# Galaxy.net
KiCad netlist of a schematic drawn in Altium Designer
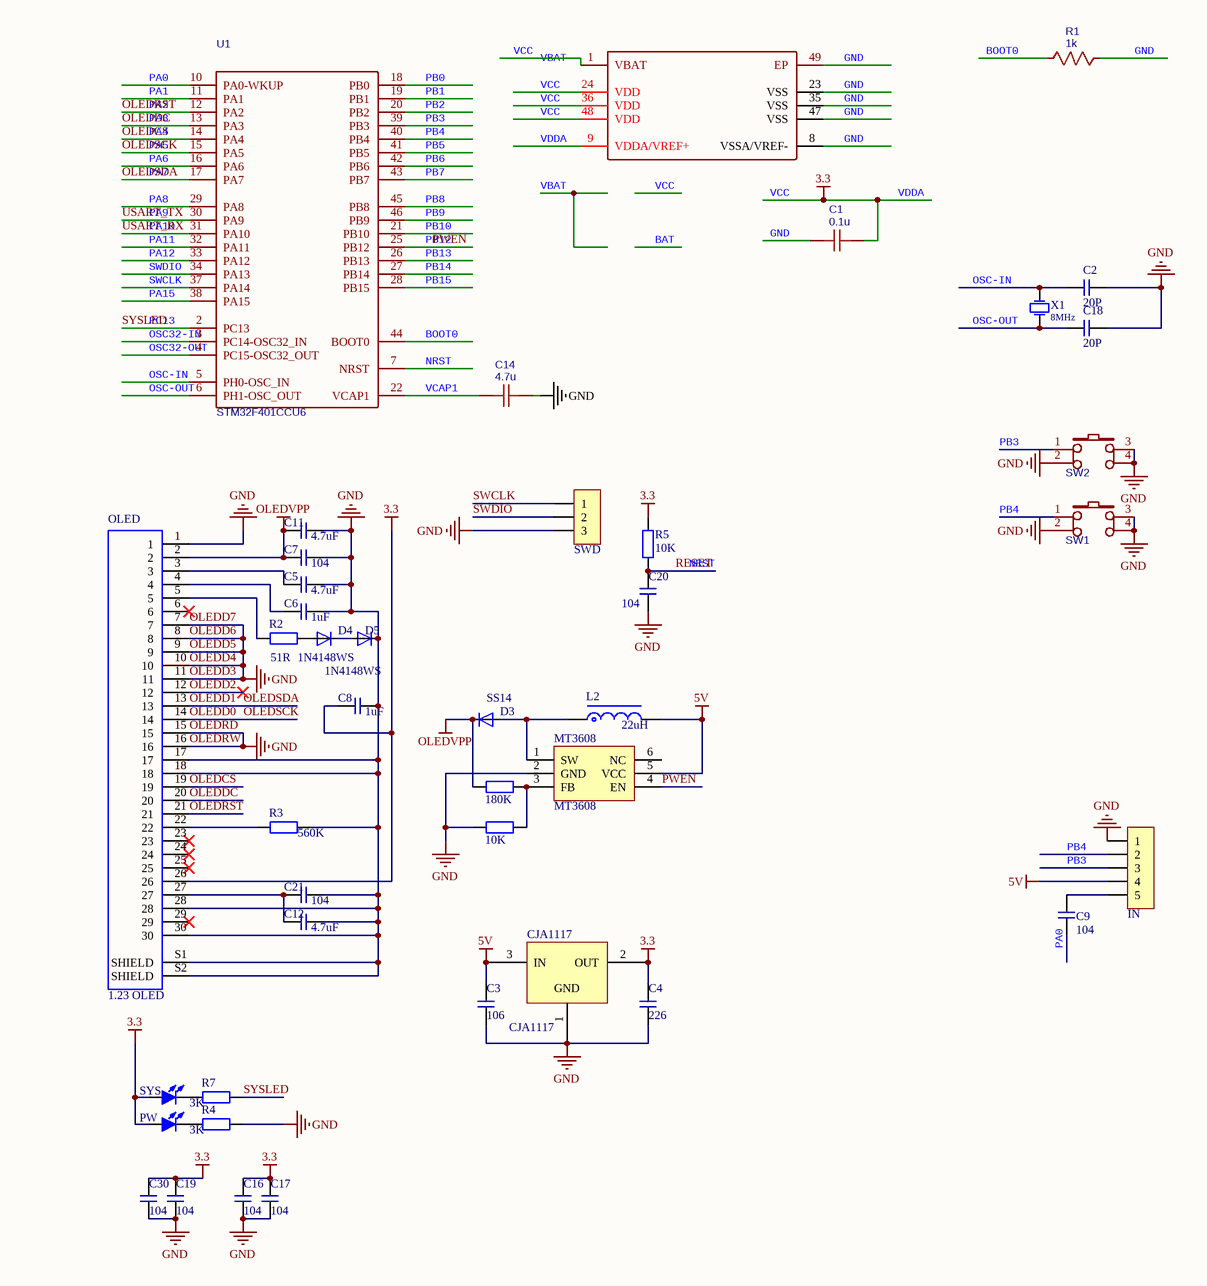
[diagram p0: Galaxy.SchDoc]

(export (version "E")
  (design (tool "Eeschema 10.0.6"))
  (components
    (comp (ref "C1")
      (value "0.1u")
      (footprint "0603C")
      (fields (field (name "CONTRIBUTOR") "LCEDA_Lib"))
      (libsource (lib "altium-import") (part "root_2_0.1u_"))
    )
    (comp (ref "C2") (value "20P") (footprint "0603C") (libsource (lib "Schlib1") (part "电容")))
    (comp (ref "C3") (value "106") (footprint "0603C") (libsource (lib "") (part "电容_1")))
    (comp (ref "C4") (value "226") (footprint "0603C") (libsource (lib "") (part "电容_1")))
    (comp (ref "C5") (value "4.7uF") (footprint "0603C") (libsource (lib "Schlib1") (part "电容")))
    (comp (ref "C6") (value "1uF") (footprint "0603C") (libsource (lib "Schlib1") (part "电容")))
    (comp (ref "C7") (value "104") (footprint "0603C") (libsource (lib "Schlib1") (part "电容")))
    (comp (ref "C8") (value "1uF") (footprint "0603C") (libsource (lib "Schlib1") (part "电容")))
    (comp (ref "C9") (value "104") (footprint "0603C") (libsource (lib "Schlib1") (part "电容")))
    (comp (ref "C11") (value "4.7uF") (footprint "0603C") (libsource (lib "Schlib1") (part "电容")))
    (comp (ref "C12") (value "4.7uF") (footprint "0603C") (libsource (lib "Schlib1") (part "电容")))
    (comp (ref "C14")
      (value "4.7u")
      (footprint "0603C")
      (fields (field (name "CONTRIBUTOR") "LCEDA_Lib"))
      (libsource (lib "altium-import") (part "root_0_4.7u_"))
    )
    (comp (ref "C16") (value "104") (footprint "0603C") (libsource (lib "Schlib1") (part "电容")))
    (comp (ref "C17") (value "104") (footprint "0603C") (libsource (lib "Schlib1") (part "电容")))
    (comp (ref "C18") (value "20P") (footprint "0603C") (libsource (lib "Schlib1") (part "电容")))
    (comp (ref "C19") (value "104") (footprint "0603C") (libsource (lib "Schlib1") (part "电容")))
    (comp (ref "C20") (value "104") (footprint "0603C") (libsource (lib "Schlib1") (part "电容")))
    (comp (ref "C21") (value "104") (footprint "0603C") (libsource (lib "Schlib1") (part "电容")))
    (comp (ref "C30") (value "104") (footprint "0603C") (libsource (lib "Schlib1") (part "电容")))
    (comp (ref "CJA1117") (value "CJA1117") (footprint "SOT-89-3") (libsource (lib "元件") (part "CJA1117")))
    (comp (ref "D3")
      (value "SS14")
      (footprint "SOD323_1N4148WS")
      (description "Diode Switching 75V 0.3A 2-Pin SOD-323 T/R")
      (fields (field (name "MF") "ON Semiconductor") (field (name "MP") "1N4148WS"))
      (libsource (lib "1N4148WS") (part "1N4148WS"))
    )
    (comp (ref "D4")
      (value "1N4148WS")
      (footprint "SOD323_1N4148WS")
      (description "Diode Switching 75V 0.3A 2-Pin SOD-323 T/R")
      (fields (field (name "MF") "ON Semiconductor"))
      (libsource (lib "1N4148WS") (part "1N4148WS"))
    )
    (comp (ref "D5")
      (value "1N4148WS")
      (footprint "SOD323_1N4148WS")
      (description "Diode Switching 75V 0.3A 2-Pin SOD-323 T/R")
      (fields (field (name "MF") "ON Semiconductor"))
      (libsource (lib "1N4148WS") (part "1N4148WS"))
    )
    (comp (ref "IN")
      (value "HDR-1X5")
      (footprint "ZH1.5-LS-5P")
      (description "5P接插件")
      (fields (field (name "版权归属") "源创客"))
      (libsource (lib "4.3   - 接插件-脚距1.5") (part "Header 5"))
    )
    (comp (ref "L2")
      (value "22uH")
      (footprint "1210-ec")
      (description "功率屏蔽电感")
      (fields (field (name "版权归属") "源创客"))
      (libsource (lib "3.1   - 电阻-电容-电感") (part "L-CDRH"))
    )
    (comp (ref "MT3608")
      (value "MT3608")
      (footprint "SOT23-6N")
      (description "可调升压芯片")
      (fields (field (name "版权归属") "源创客"))
      (libsource (lib "1.3   - 电源类芯片") (part "SX1308"))
    )
    (comp (ref "OLED")
      (value "1.23 OLED")
      (footprint "1.23 OLED")
      (description "FH12 Series 30 Position 0.5 mm Pitch Surface Mount Right Angle Flip Lock FFC/FPC")
      (fields (field (name "MF") "Hirose Electric") (field (name "MP") "FH12-30S-0.5SH_55_"))
      (libsource (lib "Nebula") (part "FH12-30S-0.5SH(55)"))
    )
    (comp (ref "PW")
      (value "白色")
      (footprint "0603LED")
      (description "方形LED")
      (fields (field (name "版权归属") "源创客"))
      (libsource (lib "9.1   - LED") (part "LED-F234"))
    )
    (comp (ref "R1")
      (value "1k")
      (footprint "0603R")
      (fields (field (name "CONTRIBUTOR") "LCEDA_Lib"))
      (libsource (lib "altium-import") (part "root_0_1k_"))
    )
    (comp (ref "R2")
      (value "51R")
      (footprint "0603R")
      (description "贴片电阻")
      (fields (field (name "版权归属") "源创客"))
      (libsource (lib "3.1   - 电阻-电容-电感") (part "R"))
    )
    (comp (ref "R3")
      (value "560K")
      (footprint "0603R")
      (description "贴片电阻")
      (fields (field (name "版权归属") "源创客"))
      (libsource (lib "3.1   - 电阻-电容-电感") (part "R"))
    )
    (comp (ref "R4")
      (value "3K")
      (footprint "0603R")
      (description "贴片电阻")
      (fields (field (name "版权归属") "源创客"))
      (libsource (lib "3.1   - 电阻-电容-电感") (part "R"))
    )
    (comp (ref "R5")
      (value "10K")
      (footprint "0603R")
      (description "贴片电阻")
      (fields (field (name "版权归属") "源创客"))
      (libsource (lib "3.1   - 电阻-电容-电感") (part "R"))
    )
    (comp (ref "R7")
      (value "3K")
      (footprint "0603R")
      (description "贴片电阻")
      (fields (field (name "版权归属") "源创客"))
      (libsource (lib "3.1   - 电阻-电容-电感") (part "R"))
    )
    (comp (ref "RB")
      (value "180K")
      (footprint "0603R")
      (description "贴片电阻")
      (fields (field (name "版权归属") "源创客"))
      (libsource (lib "3.1   - 电阻-电容-电感") (part "R"))
    )
    (comp (ref "RS")
      (value "10K")
      (footprint "0603R")
      (description "贴片电阻")
      (fields (field (name "版权归属") "源创客"))
      (libsource (lib "3.1   - 电阻-电容-电感") (part "R"))
    )
    (comp (ref "SW1")
      (value "Button-SMD-4x4x1.5")
      (footprint "SW-SMD_TS-1086E-16")
      (fields
        (field (name "BOM_SUPPLIER PART") "C71830")
        (field (name "BOM_MANUFACTURER PART") "4*4*1.5Copper head,260G, 0.25mm,")
      )
      (libsource (lib "altium-import") (part "root_0_Button-SMD-4x4x1.5_"))
    )
    (comp (ref "SW2")
      (value "Button-SMD-4x4x1.5")
      (footprint "SW-SMD_TS-1086E-16")
      (fields
        (field (name "BOM_SUPPLIER PART") "C71830")
        (field (name "BOM_MANUFACTURER PART") "4*4*1.5Copper head,260G, 0.25mm,")
      )
      (libsource (lib "altium-import") (part "root_0_Button-SMD-4x4x1.5_"))
    )
    (comp (ref "SWD")
      (value "HDR-1X3")
      (footprint "ZH1.5-LI-3P")
      (description "3P接插件")
      (fields (field (name "版权归属") "源创客"))
      (libsource (lib "4.3   - 接插件-脚距1.5") (part "Header 3"))
    )
    (comp (ref "SYS")
      (value "粉色")
      (footprint "0603LED")
      (description "方形LED")
      (fields (field (name "版权归属") "源创客"))
      (libsource (lib "9.1   - LED") (part "LED-F234"))
    )
    (comp (ref "U1")
      (value "STM32F401CCU6")
      (footprint "UFQFPN-48_L7.0-W7.0-P0.50-BL-EP")
      (fields (field (name "BOM_SUPPLIER PART") "C79861") (field (name "SUBPART_NO") "1"))
      (libsource (lib "Galaxy") (part "STM32F401CCU6"))
    )
    (comp (ref "X1")
      (value "8MHz")
      (footprint "OSC 5032-2P")
      (description "XTAL,8MHz,±20PPM,12.6*4.5")
      (fields (field (name "Comment") "1.6.1.01.005.001"))
      (libsource (lib "Mark_7") (part "1.6.1.01.005.001"))
    )
  )
  (nets
    (net (code "2") (name "/BOOT0") (class "Default")
      (node (ref "R1") (pin "1") (pinfunction "1_1") (pintype "passive"))
      (node (ref "U1") (pin "44") (pinfunction "BOOT0_44") (pintype "passive"))
    )
    (net (code "3") (name "/NRST") (class "Default")
      (node (ref "C20") (pin "1") (pinfunction "1_1") (pintype "passive"))
      (node (ref "R5") (pin "2") (pinfunction "2_2") (pintype "passive"))
      (node (ref "U1") (pin "7") (pinfunction "NRST_7") (pintype "passive"))
    )
    (net (code "4") (name "/OLEDCS") (class "Default")
      (node (ref "OLED") (pin "19") (pinfunction "19_19") (pintype "passive"))
      (node (ref "U1") (pin "14") (pinfunction "PA4_14") (pintype "passive"))
    )
    (net (code "5") (name "/OLEDD0") (class "Default")
      (node (ref "OLED") (pin "14") (pinfunction "14_14") (pintype "passive"))
      (node (ref "U1") (pin "15") (pinfunction "PA5_15") (pintype "passive"))
    )
    (net (code "6") (name "/OLEDD1") (class "Default")
      (node (ref "OLED") (pin "13") (pinfunction "13_13") (pintype "passive"))
      (node (ref "U1") (pin "17") (pinfunction "PA7_17") (pintype "passive"))
    )
    (net (code "7") (name "/OLEDD2") (class "Default")
      (node (ref "OLED") (pin "12") (pinfunction "12_12") (pintype "passive+no_connect"))
    )
    (net (code "8") (name "/OLEDDC") (class "Default")
      (node (ref "OLED") (pin "20") (pinfunction "20_20") (pintype "passive"))
      (node (ref "U1") (pin "13") (pinfunction "PA3_13") (pintype "passive"))
    )
    (net (code "9") (name "/OLEDRST") (class "Default")
      (node (ref "OLED") (pin "21") (pinfunction "21_21") (pintype "passive"))
      (node (ref "U1") (pin "12") (pinfunction "PA2_12") (pintype "passive"))
    )
    (net (code "10") (name "/OSC-IN") (class "Default")
      (node (ref "C2") (pin "2") (pinfunction "2_2") (pintype "passive"))
      (node (ref "U1") (pin "5") (pinfunction "PH0-OSC_IN_5") (pintype "passive"))
      (node (ref "X1") (pin "1") (pinfunction "OSC1_1") (pintype "passive"))
    )
    (net (code "11") (name "/OSC-OUT") (class "Default")
      (node (ref "C18") (pin "2") (pinfunction "2_2") (pintype "passive"))
      (node (ref "U1") (pin "6") (pinfunction "PH1-OSC_OUT_6") (pintype "passive"))
      (node (ref "X1") (pin "2") (pinfunction "OSC2_2") (pintype "passive"))
    )
    (net (code "12") (name "/OSC32-IN") (class "Default")
      (node (ref "U1") (pin "3") (pinfunction "PC14-OSC32_IN_3") (pintype "passive"))
    )
    (net (code "13") (name "/OSC32-OUT") (class "Default")
      (node (ref "U1") (pin "4") (pinfunction "PC15-OSC32_OUT_4") (pintype "passive"))
    )
    (net (code "14") (name "/PA0") (class "Default")
      (node (ref "C9") (pin "1") (pinfunction "1_1") (pintype "passive"))
      (node (ref "U1") (pin "10") (pinfunction "PA0-WKUP_10") (pintype "passive"))
    )
    (net (code "15") (name "/PA1") (class "Default")
      (node (ref "U1") (pin "11") (pinfunction "PA1_11") (pintype "passive"))
    )
    (net (code "16") (name "/PA6") (class "Default")
      (node (ref "U1") (pin "16") (pinfunction "PA6_16") (pintype "passive"))
    )
    (net (code "17") (name "/PA8") (class "Default")
      (node (ref "U1") (pin "29") (pinfunction "PA8_29") (pintype "passive"))
    )
    (net (code "18") (name "/PA9") (class "Default")
      (node (ref "U1") (pin "30") (pinfunction "PA9_30") (pintype "passive"))
    )
    (net (code "19") (name "/PA10") (class "Default")
      (node (ref "U1") (pin "31") (pinfunction "PA10_31") (pintype "passive"))
    )
    (net (code "20") (name "/PA11") (class "Default")
      (node (ref "U1") (pin "32") (pinfunction "PA11_32") (pintype "passive"))
    )
    (net (code "21") (name "/PA12") (class "Default")
      (node (ref "U1") (pin "33") (pinfunction "PA12_33") (pintype "passive"))
    )
    (net (code "22") (name "/PA15") (class "Default")
      (node (ref "U1") (pin "38") (pinfunction "PA15_38") (pintype "passive"))
    )
    (net (code "23") (name "/PB0") (class "Default")
      (node (ref "U1") (pin "18") (pinfunction "PB0_18") (pintype "passive"))
    )
    (net (code "24") (name "/PB1") (class "Default")
      (node (ref "U1") (pin "19") (pinfunction "PB1_19") (pintype "passive"))
    )
    (net (code "25") (name "/PB2") (class "Default")
      (node (ref "U1") (pin "20") (pinfunction "PB2_20") (pintype "passive"))
    )
    (net (code "26") (name "/PB3") (class "Default")
      (node (ref "IN") (pin "3") (pinfunction "3_3") (pintype "passive"))
      (node (ref "SW2") (pin "1") (pinfunction "1_1") (pintype "passive"))
      (node (ref "U1") (pin "39") (pinfunction "PB3_39") (pintype "passive"))
    )
    (net (code "27") (name "/PB4") (class "Default")
      (node (ref "IN") (pin "2") (pinfunction "2_2") (pintype "passive"))
      (node (ref "SW1") (pin "1") (pinfunction "1_1") (pintype "passive"))
      (node (ref "U1") (pin "40") (pinfunction "PB4_40") (pintype "passive"))
    )
    (net (code "28") (name "/PB5") (class "Default")
      (node (ref "U1") (pin "41") (pinfunction "PB5_41") (pintype "passive"))
    )
    (net (code "29") (name "/PB6") (class "Default")
      (node (ref "U1") (pin "42") (pinfunction "PB6_42") (pintype "passive"))
    )
    (net (code "30") (name "/PB7") (class "Default")
      (node (ref "U1") (pin "43") (pinfunction "PB7_43") (pintype "passive"))
    )
    (net (code "31") (name "/PB8") (class "Default")
      (node (ref "U1") (pin "45") (pinfunction "PB8_45") (pintype "passive"))
    )
    (net (code "32") (name "/PB9") (class "Default")
      (node (ref "U1") (pin "46") (pinfunction "PB9_46") (pintype "passive"))
    )
    (net (code "33") (name "/PB10") (class "Default")
      (node (ref "U1") (pin "21") (pinfunction "PB10_21") (pintype "passive"))
    )
    (net (code "34") (name "/PB12") (class "Default")
      (node (ref "MT3608") (pin "4") (pinfunction "EN_4") (pintype "passive"))
      (node (ref "U1") (pin "25") (pinfunction "PB12_25") (pintype "passive"))
    )
    (net (code "35") (name "/PB13") (class "Default")
      (node (ref "U1") (pin "26") (pinfunction "PB13_26") (pintype "passive"))
    )
    (net (code "36") (name "/PB14") (class "Default")
      (node (ref "U1") (pin "27") (pinfunction "PB14_27") (pintype "passive"))
    )
    (net (code "37") (name "/PB15") (class "Default")
      (node (ref "U1") (pin "28") (pinfunction "PB15_28") (pintype "passive"))
    )
    (net (code "38") (name "/PC13") (class "Default")
      (node (ref "R7") (pin "1") (pinfunction "1_1") (pintype "passive"))
      (node (ref "U1") (pin "2") (pinfunction "PC13_2") (pintype "passive"))
    )
    (net (code "39") (name "/SWCLK") (class "Default")
      (node (ref "SWD") (pin "1") (pinfunction "1_1") (pintype "passive"))
      (node (ref "U1") (pin "37") (pinfunction "PA14_37") (pintype "passive"))
    )
    (net (code "40") (name "/SWDIO") (class "Default")
      (node (ref "SWD") (pin "2") (pinfunction "2_2") (pintype "passive"))
      (node (ref "U1") (pin "34") (pinfunction "PA13_34") (pintype "passive"))
    )
    (net (code "42") (name "/VCAP1") (class "Default")
      (node (ref "C14") (pin "1") (pinfunction "1_1") (pintype "passive"))
      (node (ref "U1") (pin "22") (pinfunction "VCAP1_22") (pintype "passive"))
    )
    (net (code "43") (name "3.3") (class "Default")
      (node (ref "C1") (pin "1") (pinfunction "1_1") (pintype "passive"))
      (node (ref "C16") (pin "1") (pinfunction "1_1") (pintype "passive"))
      (node (ref "C17") (pin "1") (pinfunction "1_1") (pintype "passive"))
      (node (ref "C19") (pin "1") (pinfunction "1_1") (pintype "passive"))
      (node (ref "C30") (pin "1") (pinfunction "1_1") (pintype "passive"))
      (node (ref "C4") (pin "1") (pinfunction "1_1") (pintype "passive"))
      (node (ref "C8") (pin "1") (pinfunction "1_1") (pintype "passive"))
      (node (ref "CJA1117") (pin "2") (pinfunction "OUT_2") (pintype "passive"))
      (node (ref "OLED") (pin "26") (pinfunction "26_26") (pintype "passive"))
      (node (ref "PW") (pin "1") (pinfunction "A_1") (pintype "passive"))
      (node (ref "R5") (pin "1") (pinfunction "1_1") (pintype "passive"))
      (node (ref "SYS") (pin "1") (pinfunction "A_1") (pintype "passive"))
      (node (ref "U1") (pin "1") (pinfunction "VBAT_1") (pintype "passive"))
      (node (ref "U1") (pin "24") (pinfunction "VDD_24") (pintype "passive"))
      (node (ref "U1") (pin "36") (pinfunction "VDD_36") (pintype "passive"))
      (node (ref "U1") (pin "48") (pinfunction "VDD_48") (pintype "passive"))
      (node (ref "U1") (pin "9") (pinfunction "VDDA/VREF+_9") (pintype "passive"))
    )
    (net (code "44") (name "5V") (class "Default")
      (node (ref "C3") (pin "1") (pinfunction "1_1") (pintype "passive"))
      (node (ref "CJA1117") (pin "3") (pinfunction "IN_3") (pintype "passive"))
      (node (ref "IN") (pin "4") (pinfunction "4_4") (pintype "passive"))
      (node (ref "L2") (pin "2") (pinfunction "2_2") (pintype "passive"))
      (node (ref "MT3608") (pin "5") (pinfunction "VCC_5") (pintype "passive"))
    )
    (net (code "45") (name "GND") (class "Default")
      (node (ref "C1") (pin "2") (pinfunction "2_2") (pintype "passive"))
      (node (ref "C11") (pin "2") (pinfunction "2_2") (pintype "passive"))
      (node (ref "C12") (pin "2") (pinfunction "2_2") (pintype "passive"))
      (node (ref "C14") (pin "2") (pinfunction "2_2") (pintype "passive"))
      (node (ref "C16") (pin "2") (pinfunction "2_2") (pintype "passive"))
      (node (ref "C17") (pin "2") (pinfunction "2_2") (pintype "passive"))
      (node (ref "C18") (pin "1") (pinfunction "1_1") (pintype "passive"))
      (node (ref "C19") (pin "2") (pinfunction "2_2") (pintype "passive"))
      (node (ref "C2") (pin "1") (pinfunction "1_1") (pintype "passive"))
      (node (ref "C20") (pin "2") (pinfunction "2_2") (pintype "passive"))
      (node (ref "C21") (pin "2") (pinfunction "2_2") (pintype "passive"))
      (node (ref "C3") (pin "2") (pinfunction "2_2") (pintype "passive"))
      (node (ref "C30") (pin "2") (pinfunction "2_2") (pintype "passive"))
      (node (ref "C4") (pin "2") (pinfunction "2_2") (pintype "passive"))
      (node (ref "C5") (pin "2") (pinfunction "2_2") (pintype "passive"))
      (node (ref "C6") (pin "2") (pinfunction "2_2") (pintype "passive"))
      (node (ref "C7") (pin "2") (pinfunction "2_2") (pintype "passive"))
      (node (ref "C8") (pin "2") (pinfunction "2_2") (pintype "passive"))
      (node (ref "CJA1117") (pin "1") (pinfunction "GND_1") (pintype "passive"))
      (node (ref "D5") (pin "C") (pinfunction "C_C") (pintype "passive"))
      (node (ref "IN") (pin "1") (pinfunction "1_1") (pintype "passive"))
      (node (ref "MT3608") (pin "2") (pinfunction "GND_2") (pintype "passive"))
      (node (ref "OLED") (pin "1") (pinfunction "1_1") (pintype "passive"))
      (node (ref "OLED") (pin "10") (pinfunction "10_10") (pintype "passive"))
      (node (ref "OLED") (pin "11") (pinfunction "11_11") (pintype "passive"))
      (node (ref "OLED") (pin "15") (pinfunction "15_15") (pintype "passive"))
      (node (ref "OLED") (pin "16") (pinfunction "16_16") (pintype "passive"))
      (node (ref "OLED") (pin "17") (pinfunction "17_17") (pintype "passive"))
      (node (ref "OLED") (pin "18") (pinfunction "18_18") (pintype "passive"))
      (node (ref "OLED") (pin "28") (pinfunction "28_28") (pintype "passive"))
      (node (ref "OLED") (pin "30") (pinfunction "30_30") (pintype "passive"))
      (node (ref "OLED") (pin "7") (pinfunction "7_7") (pintype "passive"))
      (node (ref "OLED") (pin "8") (pinfunction "8_8") (pintype "passive"))
      (node (ref "OLED") (pin "9") (pinfunction "9_9") (pintype "passive"))
      (node (ref "OLED") (pin "S1") (pinfunction "SHIELD_S1") (pintype "passive"))
      (node (ref "OLED") (pin "S2") (pinfunction "SHIELD_S2") (pintype "passive"))
      (node (ref "R1") (pin "2") (pinfunction "2_2") (pintype "passive"))
      (node (ref "R3") (pin "1") (pinfunction "1_1") (pintype "passive"))
      (node (ref "R4") (pin "1") (pinfunction "1_1") (pintype "passive"))
      (node (ref "RS") (pin "1") (pinfunction "1_1") (pintype "passive"))
      (node (ref "SW1") (pin "2") (pinfunction "2_2") (pintype "passive"))
      (node (ref "SW1") (pin "3") (pinfunction "3_3") (pintype "passive"))
      (node (ref "SW1") (pin "4") (pinfunction "4_4") (pintype "passive"))
      (node (ref "SW2") (pin "2") (pinfunction "2_2") (pintype "passive"))
      (node (ref "SW2") (pin "3") (pinfunction "3_3") (pintype "passive"))
      (node (ref "SW2") (pin "4") (pinfunction "4_4") (pintype "passive"))
      (node (ref "SWD") (pin "3") (pinfunction "3_3") (pintype "passive"))
      (node (ref "U1") (pin "23") (pinfunction "VSS_23") (pintype "passive"))
      (node (ref "U1") (pin "35") (pinfunction "VSS_35") (pintype "passive"))
      (node (ref "U1") (pin "47") (pinfunction "VSS_47") (pintype "passive"))
      (node (ref "U1") (pin "49") (pinfunction "EP_49") (pintype "passive"))
      (node (ref "U1") (pin "8") (pinfunction "VSSA/VREF-_8") (pintype "passive"))
    )
    (net (code "46") (name "Net-(C5-Pad1)") (class "Default")
      (node (ref "C5") (pin "1") (pinfunction "1_1") (pintype "passive"))
      (node (ref "OLED") (pin "3") (pinfunction "3_3") (pintype "passive"))
    )
    (net (code "47") (name "Net-(C6-Pad1)") (class "Default")
      (node (ref "C6") (pin "1") (pinfunction "1_1") (pintype "passive"))
      (node (ref "OLED") (pin "4") (pinfunction "4_4") (pintype "passive"))
    )
    (net (code "48") (name "Net-(C9-Pad2)") (class "Default")
      (node (ref "C9") (pin "2") (pinfunction "2_2") (pintype "passive"))
      (node (ref "IN") (pin "5") (pinfunction "5_5") (pintype "passive"))
    )
    (net (code "49") (name "Net-(C12-Pad1)") (class "Default")
      (node (ref "C12") (pin "1") (pinfunction "1_1") (pintype "passive"))
      (node (ref "C21") (pin "1") (pinfunction "1_1") (pintype "passive"))
      (node (ref "OLED") (pin "27") (pinfunction "27_27") (pintype "passive"))
    )
    (net (code "50") (name "Net-(D4-PadA)") (class "Default")
      (node (ref "D4") (pin "A") (pinfunction "A_A") (pintype "passive"))
      (node (ref "R2") (pin "1") (pinfunction "1_1") (pintype "passive"))
    )
    (net (code "51") (name "Net-(D4-PadC)") (class "Default")
      (node (ref "D4") (pin "C") (pinfunction "C_C") (pintype "passive"))
      (node (ref "D5") (pin "A") (pinfunction "A_A") (pintype "passive"))
    )
    (net (code "52") (name "Net-(MT3608-FB)") (class "Default")
      (node (ref "MT3608") (pin "3") (pinfunction "FB_3") (pintype "passive"))
      (node (ref "RB") (pin "2") (pinfunction "2_2") (pintype "passive"))
      (node (ref "RS") (pin "2") (pinfunction "2_2") (pintype "passive"))
    )
    (net (code "53") (name "Net-(MT3608-SW)") (class "Default")
      (node (ref "D3") (pin "A") (pinfunction "A_A") (pintype "passive"))
      (node (ref "L2") (pin "1") (pinfunction "1_1") (pintype "passive"))
      (node (ref "MT3608") (pin "1") (pinfunction "SW_1") (pintype "passive"))
    )
    (net (code "54") (name "Net-(OLED-Pad5)") (class "Default")
      (node (ref "OLED") (pin "5") (pinfunction "5_5") (pintype "passive"))
      (node (ref "R2") (pin "2") (pinfunction "2_2") (pintype "passive"))
    )
    (net (code "55") (name "Net-(OLED-Pad22)") (class "Default")
      (node (ref "OLED") (pin "22") (pinfunction "22_22") (pintype "passive"))
      (node (ref "R3") (pin "2") (pinfunction "2_2") (pintype "passive"))
    )
    (net (code "56") (name "Net-(PW-K)") (class "Default")
      (node (ref "PW") (pin "2") (pinfunction "K_2") (pintype "passive"))
      (node (ref "R4") (pin "2") (pinfunction "2_2") (pintype "passive"))
    )
    (net (code "57") (name "Net-(SYS-K)") (class "Default")
      (node (ref "R7") (pin "2") (pinfunction "2_2") (pintype "passive"))
      (node (ref "SYS") (pin "2") (pinfunction "K_2") (pintype "passive"))
    )
    (net (code "58") (name "OLEDVPP") (class "Default")
      (node (ref "C11") (pin "1") (pinfunction "1_1") (pintype "passive"))
      (node (ref "C7") (pin "1") (pinfunction "1_1") (pintype "passive"))
      (node (ref "D3") (pin "C") (pinfunction "C_C") (pintype "passive"))
      (node (ref "OLED") (pin "2") (pinfunction "2_2") (pintype "passive"))
      (node (ref "RB") (pin "1") (pinfunction "1_1") (pintype "passive"))
    )
    (net (code "59") (name "unconnected-(MT3608-NC-Pad6)") (class "Default")
      (node (ref "MT3608") (pin "6") (pinfunction "NC_6") (pintype "passive"))
    )
    (net (code "60") (name "unconnected-(OLED-Pad6)") (class "Default")
      (node (ref "OLED") (pin "6") (pinfunction "6_6") (pintype "passive+no_connect"))
    )
    (net (code "61") (name "unconnected-(OLED-Pad23)") (class "Default")
      (node (ref "OLED") (pin "23") (pinfunction "23_23") (pintype "passive+no_connect"))
    )
    (net (code "62") (name "unconnected-(OLED-Pad24)") (class "Default")
      (node (ref "OLED") (pin "24") (pinfunction "24_24") (pintype "passive+no_connect"))
    )
    (net (code "63") (name "unconnected-(OLED-Pad25)") (class "Default")
      (node (ref "OLED") (pin "25") (pinfunction "25_25") (pintype "passive+no_connect"))
    )
    (net (code "64") (name "unconnected-(OLED-Pad29)") (class "Default")
      (node (ref "OLED") (pin "29") (pinfunction "29_29") (pintype "passive+no_connect"))
    )
  )
)
